# board.net
KiCad netlist of a schematic drawn in EAGLE
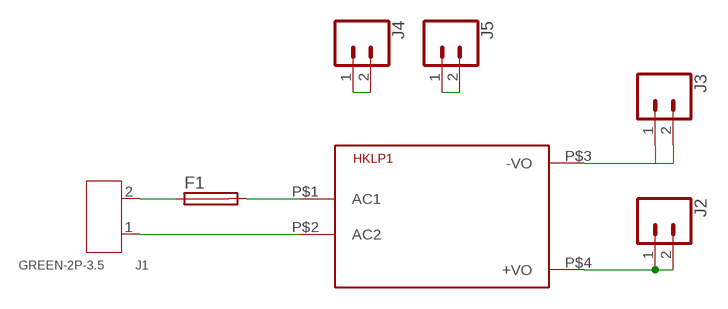
[diagram p0: schematic, sheet 1]

(export (version "E")
  (design (tool "Eeschema 10.0.6"))
  (components
    (comp (ref "F1")
      (value "TR5")
      (footprint "eagle-import:TR5")
      (libsource (lib "eagle-import") (part "TR5"))
    )
    (comp (ref "HKLP1")
      (value "HKLPM01")
      (footprint "eagle-import:HKLPM01")
      (libsource (lib "eagle-import") (part "HKLPM01"))
    )
    (comp (ref "J1")
      (value "GREEN-2P-3.5")
      (footprint "eagle-import:H2-3.5-7.0X7.0MM")
      (libsource (lib "eagle-import") (part "SCREW-TERMINAL-GREEN(2P-3.5)"))
    )
    (comp (ref "J2")
      (value "CONN_02")
      (footprint "eagle-import:1X02")
      (libsource (lib "eagle-import") (part "CONN_02"))
    )
    (comp (ref "J3")
      (value "CONN_02")
      (footprint "eagle-import:1X02")
      (libsource (lib "eagle-import") (part "CONN_02"))
    )
    (comp (ref "J4")
      (value "CONN_02")
      (footprint "eagle-import:1X02")
      (libsource (lib "eagle-import") (part "CONN_02"))
    )
    (comp (ref "J5")
      (value "CONN_02")
      (footprint "eagle-import:1X02")
      (libsource (lib "eagle-import") (part "CONN_02"))
    )
  )
  (nets
    (net (code "1") (name "Net-(F1-Pad1)") (class "Default")
      (node (ref "F1") (pin "1") (pinfunction "1_1") (pintype "passive"))
      (node (ref "J1") (pin "2") (pinfunction "2_2") (pintype "bidirectional"))
    )
    (net (code "2") (name "Net-(HKLP1-+VO)") (class "Default")
      (node (ref "HKLP1") (pin "P$4") (pinfunction "+VO_P$4") (pintype "bidirectional"))
      (node (ref "J2") (pin "1") (pinfunction "1_1") (pintype "passive"))
      (node (ref "J2") (pin "2") (pinfunction "2_2") (pintype "passive"))
    )
    (net (code "3") (name "Net-(HKLP1--VO)") (class "Default")
      (node (ref "HKLP1") (pin "P$3") (pinfunction "-VO_P$3") (pintype "bidirectional"))
      (node (ref "J3") (pin "1") (pinfunction "1_1") (pintype "passive"))
      (node (ref "J3") (pin "2") (pinfunction "2_2") (pintype "passive"))
    )
    (net (code "4") (name "Net-(HKLP1-AC1)") (class "Default")
      (node (ref "F1") (pin "2") (pinfunction "2_2") (pintype "passive"))
      (node (ref "HKLP1") (pin "P$1") (pinfunction "AC1_P$1") (pintype "bidirectional"))
    )
    (net (code "5") (name "Net-(HKLP1-AC2)") (class "Default")
      (node (ref "HKLP1") (pin "P$2") (pinfunction "AC2_P$2") (pintype "bidirectional"))
      (node (ref "J1") (pin "1") (pinfunction "1_1") (pintype "bidirectional"))
    )
    (net (code "6") (name "Net-(J4-Pad1)") (class "Default")
      (node (ref "J4") (pin "1") (pinfunction "1_1") (pintype "passive"))
      (node (ref "J4") (pin "2") (pinfunction "2_2") (pintype "passive"))
    )
    (net (code "7") (name "Net-(J5-Pad1)") (class "Default")
      (node (ref "J5") (pin "1") (pinfunction "1_1") (pintype "passive"))
      (node (ref "J5") (pin "2") (pinfunction "2_2") (pintype "passive"))
    )
  )
)
